# board.net
KiCad netlist of a schematic drawn in EAGLE
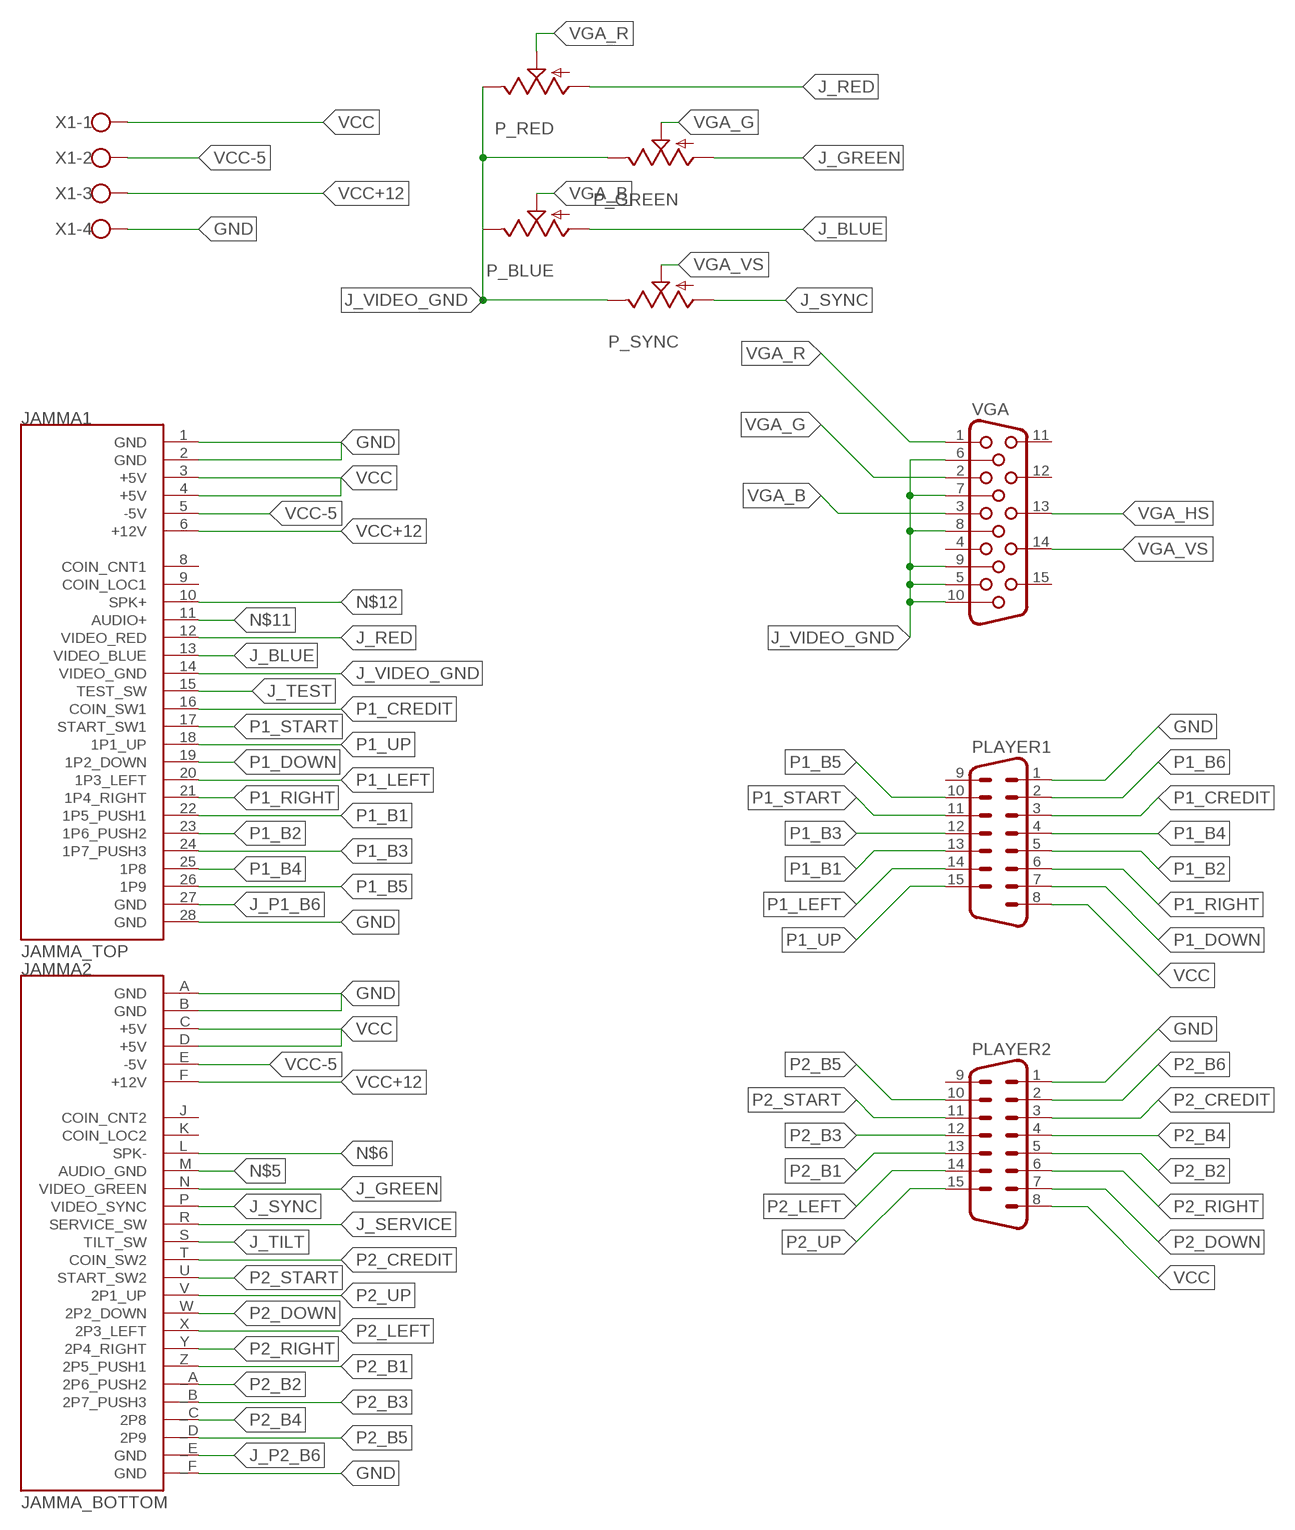
[diagram p0: schematic, sheet 1]

(export (version "E")
  (design (tool "Eeschema 10.0.6"))
  (components
    (comp (ref "JAMMA1")
      (value "JAMMA_TOP")
      (footprint "eagle-import:JAMMA_TOP")
      (libsource (lib "eagle-import") (part "JAMMA_TOP"))
    )
    (comp (ref "JAMMA2")
      (value "JAMMA_BOTTOM")
      (footprint "eagle-import:JAMMA_BOTTOM")
      (libsource (lib "eagle-import") (part "JAMMA_BOTTOM"))
    )
    (comp (ref "PLAYER1")
      (value "M15VB")
      (footprint "eagle-import:M15VB")
      (libsource (lib "eagle-import") (part "M15VB"))
    )
    (comp (ref "PLAYER2")
      (value "M15VB")
      (footprint "eagle-import:M15VB")
      (libsource (lib "eagle-import") (part "M15VB"))
    )
    (comp (ref "P_BLUE")
      (value "TRIM_US-B25P")
      (footprint "eagle-import:B25P")
      (libsource (lib "eagle-import") (part "TRIM_US-B25P"))
    )
    (comp (ref "P_GREEN")
      (value "TRIM_US-B25P")
      (footprint "eagle-import:B25P")
      (libsource (lib "eagle-import") (part "TRIM_US-B25P"))
    )
    (comp (ref "P_RED")
      (value "TRIM_US-B25P")
      (footprint "eagle-import:B25P")
      (libsource (lib "eagle-import") (part "TRIM_US-B25P"))
    )
    (comp (ref "P_SYNC")
      (value "TRIM_US-B25P")
      (footprint "eagle-import:B25P")
      (libsource (lib "eagle-import") (part "TRIM_US-B25P"))
    )
    (comp (ref "VGA")
      (value "HF15H")
      (footprint "eagle-import:HDF15H")
      (libsource (lib "eagle-import") (part "HF15H"))
    )
    (comp (ref "X1")
      (value "W237-4")
      (footprint "eagle-import:W237-4")
      (libsource (lib "eagle-import") (part "W237-4"))
    )
  )
  (nets
    (net (code "1") (name "GND") (class "Default")
      (node (ref "JAMMA1") (pin "1") (pinfunction "GND_1") (pintype "power_in"))
      (node (ref "JAMMA1") (pin "2") (pinfunction "GND_2") (pintype "power_in"))
      (node (ref "JAMMA1") (pin "28") (pinfunction "GND_28") (pintype "power_in"))
      (node (ref "JAMMA2") (pin "A") (pinfunction "GND_A") (pintype "power_in"))
      (node (ref "JAMMA2") (pin "B") (pinfunction "GND_B") (pintype "power_in"))
      (node (ref "JAMMA2") (pin "_F") (pinfunction "GND__F") (pintype "power_in"))
      (node (ref "PLAYER1") (pin "1") (pinfunction "1_1") (pintype "passive"))
      (node (ref "PLAYER2") (pin "1") (pinfunction "1_1") (pintype "passive"))
      (node (ref "X1") (pin "4") (pinfunction "KL_4") (pintype "passive"))
    )
    (net (code "2") (name "J_BLUE") (class "Default")
      (node (ref "JAMMA1") (pin "13") (pinfunction "VIDEO_BLUE_13") (pintype "output"))
      (node (ref "P_BLUE") (pin "A") (pinfunction "A_A") (pintype "passive"))
    )
    (net (code "3") (name "J_GREEN") (class "Default")
      (node (ref "JAMMA2") (pin "N") (pinfunction "VIDEO_GREEN_N") (pintype "output"))
      (node (ref "P_GREEN") (pin "A") (pinfunction "A_A") (pintype "passive"))
    )
    (net (code "4") (name "J_P1_B6") (class "Default")
      (node (ref "JAMMA1") (pin "27") (pinfunction "GND_27") (pintype "power_in"))
    )
    (net (code "5") (name "J_P2_B6") (class "Default")
      (node (ref "JAMMA2") (pin "_E") (pinfunction "GND__E") (pintype "power_in"))
    )
    (net (code "6") (name "J_RED") (class "Default")
      (node (ref "JAMMA1") (pin "12") (pinfunction "VIDEO_RED_12") (pintype "output"))
      (node (ref "P_RED") (pin "A") (pinfunction "A_A") (pintype "passive"))
    )
    (net (code "7") (name "J_SERVICE") (class "Default")
      (node (ref "JAMMA2") (pin "R") (pinfunction "SERVICE_SW_R") (pintype "input"))
    )
    (net (code "8") (name "J_SYNC") (class "Default")
      (node (ref "JAMMA2") (pin "P") (pinfunction "VIDEO_SYNC_P") (pintype "output"))
      (node (ref "P_SYNC") (pin "A") (pinfunction "A_A") (pintype "passive"))
    )
    (net (code "9") (name "J_TEST") (class "Default")
      (node (ref "JAMMA1") (pin "15") (pinfunction "TEST_SW_15") (pintype "input"))
    )
    (net (code "10") (name "J_TILT") (class "Default")
      (node (ref "JAMMA2") (pin "S") (pinfunction "TILT_SW_S") (pintype "input"))
    )
    (net (code "11") (name "J_VIDEO_GND") (class "Default")
      (node (ref "JAMMA1") (pin "14") (pinfunction "VIDEO_GND_14") (pintype "output"))
      (node (ref "P_BLUE") (pin "E") (pinfunction "E_E") (pintype "passive"))
      (node (ref "P_GREEN") (pin "E") (pinfunction "E_E") (pintype "passive"))
      (node (ref "P_RED") (pin "E") (pinfunction "E_E") (pintype "passive"))
      (node (ref "P_SYNC") (pin "E") (pinfunction "E_E") (pintype "passive"))
      (node (ref "VGA") (pin "10") (pinfunction "10_10") (pintype "passive"))
      (node (ref "VGA") (pin "5") (pinfunction "5_5") (pintype "passive"))
      (node (ref "VGA") (pin "6") (pinfunction "6_6") (pintype "passive"))
      (node (ref "VGA") (pin "7") (pinfunction "7_7") (pintype "passive"))
      (node (ref "VGA") (pin "8") (pinfunction "8_8") (pintype "passive"))
      (node (ref "VGA") (pin "9") (pinfunction "9_9") (pintype "passive"))
    )
    (net (code "12") (name "N$5") (class "Default")
      (node (ref "JAMMA2") (pin "M") (pinfunction "AUDIO_GND_M") (pintype "output"))
    )
    (net (code "13") (name "N$6") (class "Default")
      (node (ref "JAMMA2") (pin "L") (pinfunction "SPK-_L") (pintype "output"))
    )
    (net (code "14") (name "N$11") (class "Default")
      (node (ref "JAMMA1") (pin "11") (pinfunction "AUDIO+_11") (pintype "output"))
    )
    (net (code "15") (name "N$12") (class "Default")
      (node (ref "JAMMA1") (pin "10") (pinfunction "SPK+_10") (pintype "output"))
    )
    (net (code "16") (name "P1_B1") (class "Default")
      (node (ref "JAMMA1") (pin "22") (pinfunction "1P5_PUSH1_22") (pintype "input"))
      (node (ref "PLAYER1") (pin "13") (pinfunction "13_13") (pintype "passive"))
    )
    (net (code "17") (name "P1_B2") (class "Default")
      (node (ref "JAMMA1") (pin "23") (pinfunction "1P6_PUSH2_23") (pintype "input"))
      (node (ref "PLAYER1") (pin "5") (pinfunction "5_5") (pintype "passive"))
    )
    (net (code "18") (name "P1_B3") (class "Default")
      (node (ref "JAMMA1") (pin "24") (pinfunction "1P7_PUSH3_24") (pintype "input"))
      (node (ref "PLAYER1") (pin "12") (pinfunction "12_12") (pintype "passive"))
    )
    (net (code "19") (name "P1_B4") (class "Default")
      (node (ref "JAMMA1") (pin "25") (pinfunction "1P8_25") (pintype "input"))
      (node (ref "PLAYER1") (pin "4") (pinfunction "4_4") (pintype "passive"))
    )
    (net (code "20") (name "P1_B5") (class "Default")
      (node (ref "JAMMA1") (pin "26") (pinfunction "1P9_26") (pintype "input"))
      (node (ref "PLAYER1") (pin "10") (pinfunction "10_10") (pintype "passive"))
    )
    (net (code "21") (name "P1_B6") (class "Default")
      (node (ref "PLAYER1") (pin "2") (pinfunction "2_2") (pintype "passive"))
    )
    (net (code "22") (name "P1_CREDIT") (class "Default")
      (node (ref "JAMMA1") (pin "16") (pinfunction "COIN_SW1_16") (pintype "input"))
      (node (ref "PLAYER1") (pin "3") (pinfunction "3_3") (pintype "passive"))
    )
    (net (code "23") (name "P1_DOWN") (class "Default")
      (node (ref "JAMMA1") (pin "19") (pinfunction "1P2_DOWN_19") (pintype "input"))
      (node (ref "PLAYER1") (pin "7") (pinfunction "7_7") (pintype "passive"))
    )
    (net (code "24") (name "P1_LEFT") (class "Default")
      (node (ref "JAMMA1") (pin "20") (pinfunction "1P3_LEFT_20") (pintype "input"))
      (node (ref "PLAYER1") (pin "14") (pinfunction "14_14") (pintype "passive"))
    )
    (net (code "25") (name "P1_RIGHT") (class "Default")
      (node (ref "JAMMA1") (pin "21") (pinfunction "1P4_RIGHT_21") (pintype "input"))
      (node (ref "PLAYER1") (pin "6") (pinfunction "6_6") (pintype "passive"))
    )
    (net (code "26") (name "P1_START") (class "Default")
      (node (ref "JAMMA1") (pin "17") (pinfunction "START_SW1_17") (pintype "input"))
      (node (ref "PLAYER1") (pin "11") (pinfunction "11_11") (pintype "passive"))
    )
    (net (code "27") (name "P1_UP") (class "Default")
      (node (ref "JAMMA1") (pin "18") (pinfunction "1P1_UP_18") (pintype "input"))
      (node (ref "PLAYER1") (pin "15") (pinfunction "15_15") (pintype "passive"))
    )
    (net (code "28") (name "P2_B1") (class "Default")
      (node (ref "JAMMA2") (pin "Z") (pinfunction "2P5_PUSH1_Z") (pintype "input"))
      (node (ref "PLAYER2") (pin "13") (pinfunction "13_13") (pintype "passive"))
    )
    (net (code "29") (name "P2_B2") (class "Default")
      (node (ref "JAMMA2") (pin "_A") (pinfunction "2P6_PUSH2__A") (pintype "input"))
      (node (ref "PLAYER2") (pin "5") (pinfunction "5_5") (pintype "passive"))
    )
    (net (code "30") (name "P2_B3") (class "Default")
      (node (ref "JAMMA2") (pin "_B") (pinfunction "2P7_PUSH3__B") (pintype "input"))
      (node (ref "PLAYER2") (pin "12") (pinfunction "12_12") (pintype "passive"))
    )
    (net (code "31") (name "P2_B4") (class "Default")
      (node (ref "JAMMA2") (pin "_C") (pinfunction "2P8__C") (pintype "input"))
      (node (ref "PLAYER2") (pin "4") (pinfunction "4_4") (pintype "passive"))
    )
    (net (code "32") (name "P2_B5") (class "Default")
      (node (ref "JAMMA2") (pin "_D") (pinfunction "2P9__D") (pintype "input"))
      (node (ref "PLAYER2") (pin "10") (pinfunction "10_10") (pintype "passive"))
    )
    (net (code "33") (name "P2_B6") (class "Default")
      (node (ref "PLAYER2") (pin "2") (pinfunction "2_2") (pintype "passive"))
    )
    (net (code "34") (name "P2_CREDIT") (class "Default")
      (node (ref "JAMMA2") (pin "T") (pinfunction "COIN_SW2_T") (pintype "input"))
      (node (ref "PLAYER2") (pin "3") (pinfunction "3_3") (pintype "passive"))
    )
    (net (code "35") (name "P2_DOWN") (class "Default")
      (node (ref "JAMMA2") (pin "W") (pinfunction "2P2_DOWN_W") (pintype "input"))
      (node (ref "PLAYER2") (pin "7") (pinfunction "7_7") (pintype "passive"))
    )
    (net (code "36") (name "P2_LEFT") (class "Default")
      (node (ref "JAMMA2") (pin "X") (pinfunction "2P3_LEFT_X") (pintype "input"))
      (node (ref "PLAYER2") (pin "14") (pinfunction "14_14") (pintype "passive"))
    )
    (net (code "37") (name "P2_RIGHT") (class "Default")
      (node (ref "JAMMA2") (pin "Y") (pinfunction "2P4_RIGHT_Y") (pintype "input"))
      (node (ref "PLAYER2") (pin "6") (pinfunction "6_6") (pintype "passive"))
    )
    (net (code "38") (name "P2_START") (class "Default")
      (node (ref "JAMMA2") (pin "U") (pinfunction "START_SW2_U") (pintype "input"))
      (node (ref "PLAYER2") (pin "11") (pinfunction "11_11") (pintype "passive"))
    )
    (net (code "39") (name "P2_UP") (class "Default")
      (node (ref "JAMMA2") (pin "V") (pinfunction "2P1_UP_V") (pintype "input"))
      (node (ref "PLAYER2") (pin "15") (pinfunction "15_15") (pintype "passive"))
    )
    (net (code "40") (name "VCC") (class "Default")
      (node (ref "JAMMA1") (pin "3") (pinfunction "+5V_3") (pintype "power_in"))
      (node (ref "JAMMA1") (pin "4") (pinfunction "+5V_4") (pintype "power_in"))
      (node (ref "JAMMA2") (pin "C") (pinfunction "+5V_C") (pintype "power_in"))
      (node (ref "JAMMA2") (pin "D") (pinfunction "+5V_D") (pintype "power_in"))
      (node (ref "PLAYER1") (pin "8") (pinfunction "8_8") (pintype "passive"))
      (node (ref "PLAYER2") (pin "8") (pinfunction "8_8") (pintype "passive"))
      (node (ref "X1") (pin "1") (pinfunction "KL_1") (pintype "passive"))
    )
    (net (code "41") (name "VCC+12") (class "Default")
      (node (ref "JAMMA1") (pin "6") (pinfunction "+12V_6") (pintype "power_in"))
      (node (ref "JAMMA2") (pin "F") (pinfunction "+12V_F") (pintype "power_in"))
      (node (ref "X1") (pin "3") (pinfunction "KL_3") (pintype "passive"))
    )
    (net (code "42") (name "VCC-5") (class "Default")
      (node (ref "JAMMA1") (pin "5") (pinfunction "-5V_5") (pintype "power_in"))
      (node (ref "JAMMA2") (pin "E") (pinfunction "-5V_E") (pintype "power_in"))
      (node (ref "X1") (pin "2") (pinfunction "KL_2") (pintype "passive"))
    )
    (net (code "43") (name "VGA_B") (class "Default")
      (node (ref "P_BLUE") (pin "S") (pinfunction "S_S") (pintype "passive"))
      (node (ref "VGA") (pin "3") (pinfunction "3_3") (pintype "passive"))
    )
    (net (code "44") (name "VGA_G") (class "Default")
      (node (ref "P_GREEN") (pin "S") (pinfunction "S_S") (pintype "passive"))
      (node (ref "VGA") (pin "2") (pinfunction "2_2") (pintype "passive"))
    )
    (net (code "45") (name "VGA_HS") (class "Default")
      (node (ref "VGA") (pin "13") (pinfunction "13_13") (pintype "passive"))
    )
    (net (code "46") (name "VGA_R") (class "Default")
      (node (ref "P_RED") (pin "S") (pinfunction "S_S") (pintype "passive"))
      (node (ref "VGA") (pin "1") (pinfunction "1_1") (pintype "passive"))
    )
    (net (code "47") (name "VGA_VS") (class "Default")
      (node (ref "P_SYNC") (pin "S") (pinfunction "S_S") (pintype "passive"))
      (node (ref "VGA") (pin "14") (pinfunction "14_14") (pintype "passive"))
    )
    (net (code "48") (name "unconnected-(JAMMA1-COIN_CNT1-Pad8)") (class "Default")
      (node (ref "JAMMA1") (pin "8") (pinfunction "COIN_CNT1_8") (pintype "output"))
    )
    (net (code "49") (name "unconnected-(JAMMA1-COIN_LOC1-Pad9)") (class "Default")
      (node (ref "JAMMA1") (pin "9") (pinfunction "COIN_LOC1_9") (pintype "output"))
    )
    (net (code "50") (name "unconnected-(JAMMA2-COIN_CNT2-PadJ)") (class "Default")
      (node (ref "JAMMA2") (pin "J") (pinfunction "COIN_CNT2_J") (pintype "output"))
    )
    (net (code "51") (name "unconnected-(JAMMA2-COIN_LOC2-PadK)") (class "Default")
      (node (ref "JAMMA2") (pin "K") (pinfunction "COIN_LOC2_K") (pintype "output"))
    )
    (net (code "52") (name "unconnected-(PLAYER1-Pad9)") (class "Default")
      (node (ref "PLAYER1") (pin "9") (pinfunction "9_9") (pintype "passive"))
    )
    (net (code "53") (name "unconnected-(PLAYER2-Pad9)") (class "Default")
      (node (ref "PLAYER2") (pin "9") (pinfunction "9_9") (pintype "passive"))
    )
    (net (code "54") (name "unconnected-(VGA-Pad4)") (class "Default")
      (node (ref "VGA") (pin "4") (pinfunction "4_4") (pintype "passive"))
    )
    (net (code "55") (name "unconnected-(VGA-Pad11)") (class "Default")
      (node (ref "VGA") (pin "11") (pinfunction "11_11") (pintype "passive"))
    )
    (net (code "56") (name "unconnected-(VGA-Pad12)") (class "Default")
      (node (ref "VGA") (pin "12") (pinfunction "12_12") (pintype "passive"))
    )
    (net (code "57") (name "unconnected-(VGA-Pad15)") (class "Default")
      (node (ref "VGA") (pin "15") (pinfunction "15_15") (pintype "passive"))
    )
  )
)
